# Arduino-Pro-Mini-v10.net
KiCad netlist of a schematic drawn in EAGLE
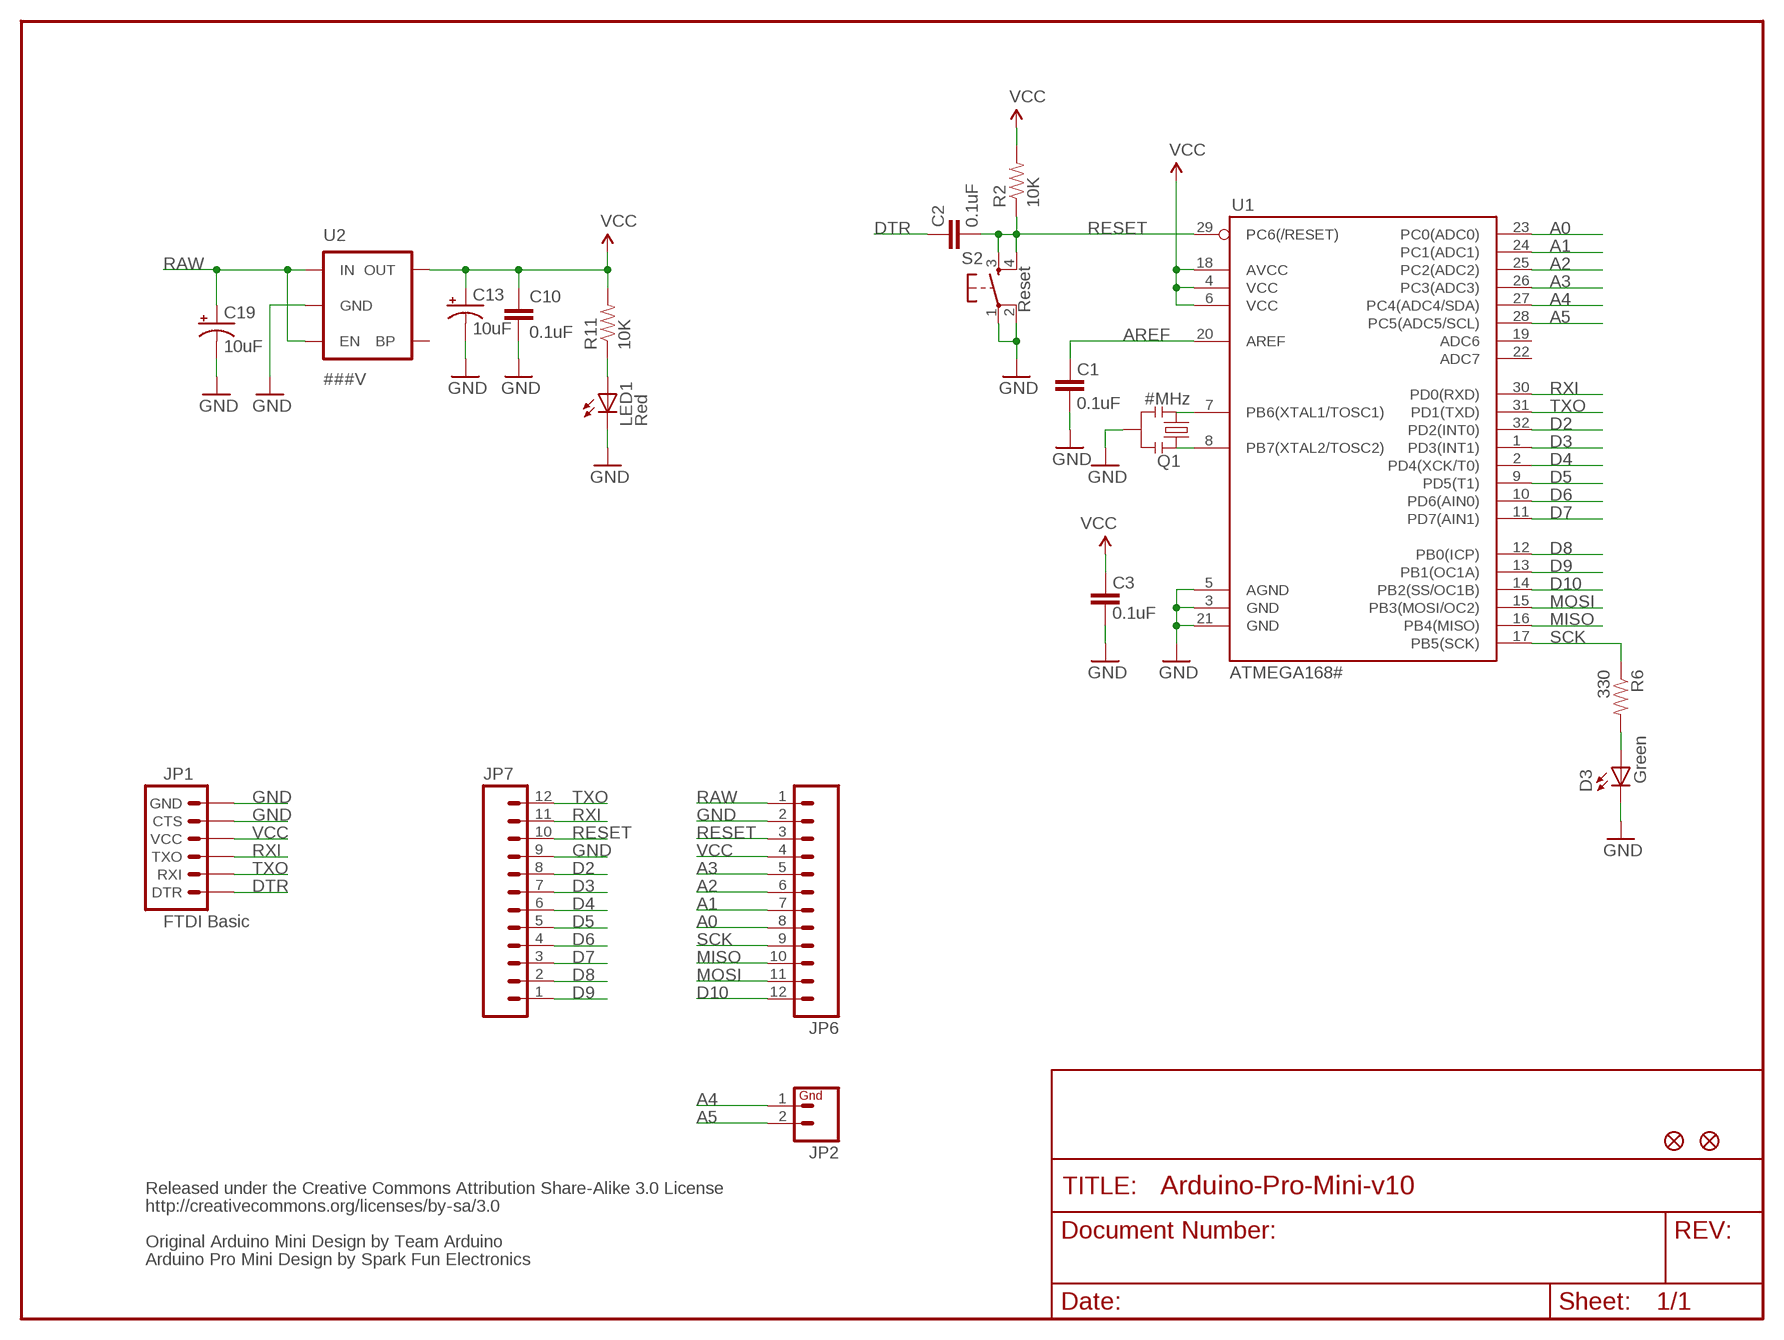
[diagram p0: schematic, sheet 1]

(export (version "E")
  (design (tool "Eeschema 10.0.6"))
  (components
    (comp (ref "C1")
      (value "0.1uF")
      (footprint "eagle-import:C0402")
      (libsource (lib "eagle-import") (part "CAP0402"))
    )
    (comp (ref "C2")
      (value "0.1uF")
      (footprint "eagle-import:C0402")
      (libsource (lib "eagle-import") (part "CAP0402"))
    )
    (comp (ref "C3")
      (value "0.1uF")
      (footprint "eagle-import:C0402")
      (libsource (lib "eagle-import") (part "CAP0402"))
    )
    (comp (ref "C10")
      (value "0.1uF")
      (footprint "eagle-import:C0402")
      (libsource (lib "eagle-import") (part "CAP0402"))
    )
    (comp (ref "C13")
      (value "10uF")
      (footprint "eagle-import:EIA3216")
      (libsource (lib "eagle-import") (part "CAP_POL1206"))
    )
    (comp (ref "C19")
      (value "10uF")
      (footprint "eagle-import:EIA3216")
      (libsource (lib "eagle-import") (part "CAP_POL1206"))
    )
    (comp (ref "D3")
      (value "Green")
      (footprint "eagle-import:LED-0603")
      (libsource (lib "eagle-import") (part "LED0603"))
    )
    (comp (ref "JP1")
      (value "FTDI Basic")
      (footprint "eagle-import:1X06")
      (libsource (lib "eagle-import") (part "ARDUINO_SERIAL_PROGRAMPTH"))
    )
    (comp (ref "JP2")
      (value "M02PTH")
      (footprint "eagle-import:1X02")
      (libsource (lib "eagle-import") (part "M02PTH"))
    )
    (comp (ref "JP6")
      (value "M12PTH")
      (footprint "eagle-import:1X12")
      (libsource (lib "eagle-import") (part "M12PTH"))
    )
    (comp (ref "JP7")
      (value "M12PTH")
      (footprint "eagle-import:1X12")
      (libsource (lib "eagle-import") (part "M12PTH"))
    )
    (comp (ref "LED1")
      (value "Red")
      (footprint "eagle-import:LED-0603")
      (libsource (lib "eagle-import") (part "LED0603"))
    )
    (comp (ref "Q1")
      (value "#MHz")
      (footprint "eagle-import:RESONATOR-SMD")
      (libsource (lib "eagle-import") (part "RESONATORSMD"))
    )
    (comp (ref "R2")
      (value "10K")
      (footprint "eagle-import:C0402")
      (libsource (lib "eagle-import") (part "RESISTOR0402"))
    )
    (comp (ref "R6")
      (value "330")
      (footprint "eagle-import:C0402")
      (libsource (lib "eagle-import") (part "RESISTOR0402"))
    )
    (comp (ref "R11")
      (value "10K")
      (footprint "eagle-import:C0402")
      (libsource (lib "eagle-import") (part "RESISTOR0402"))
    )
    (comp (ref "S2")
      (value "Reset")
      (footprint "eagle-import:TACTILE_SWITCH_SMD")
      (libsource (lib "eagle-import") (part "TAC_SWITCHSND"))
    )
    (comp (ref "U$2")
      (value "FIDUCIAL1X2")
      (footprint "eagle-import:FIDUCIAL-1X2")
      (libsource (lib "eagle-import") (part "FIDUCIAL1X2"))
    )
    (comp (ref "U$4")
      (value "FIDUCIAL1X2")
      (footprint "eagle-import:FIDUCIAL-1X2")
      (libsource (lib "eagle-import") (part "FIDUCIAL1X2"))
    )
    (comp (ref "U1")
      (value "ATMEGA168#")
      (footprint "eagle-import:TQFP32-08")
      (libsource (lib "eagle-import") (part "ATMEGA168"))
    )
    (comp (ref "U2")
      (value "###V")
      (footprint "eagle-import:SOT23-5")
      (libsource (lib "eagle-import") (part "V_REG_LDOSMD"))
    )
  )
  (nets
    (net (code "1") (name "/A0") (class "Default")
      (node (ref "JP6") (pin "8") (pinfunction "8_8") (pintype "passive"))
      (node (ref "U1") (pin "23") (pinfunction "PC0(ADC0)_23") (pintype "bidirectional"))
    )
    (net (code "2") (name "/A1") (class "Default")
      (node (ref "JP6") (pin "7") (pinfunction "7_7") (pintype "passive"))
      (node (ref "U1") (pin "24") (pinfunction "PC1(ADC1)_24") (pintype "bidirectional"))
    )
    (net (code "3") (name "/A2") (class "Default")
      (node (ref "JP6") (pin "6") (pinfunction "6_6") (pintype "passive"))
      (node (ref "U1") (pin "25") (pinfunction "PC2(ADC2)_25") (pintype "bidirectional"))
    )
    (net (code "4") (name "/A3") (class "Default")
      (node (ref "JP6") (pin "5") (pinfunction "5_5") (pintype "passive"))
      (node (ref "U1") (pin "26") (pinfunction "PC3(ADC3)_26") (pintype "bidirectional"))
    )
    (net (code "5") (name "/A4") (class "Default")
      (node (ref "JP2") (pin "1") (pinfunction "1_1") (pintype "passive"))
      (node (ref "U1") (pin "27") (pinfunction "PC4(ADC4/SDA)_27") (pintype "bidirectional"))
    )
    (net (code "6") (name "/A5") (class "Default")
      (node (ref "JP2") (pin "2") (pinfunction "2_2") (pintype "passive"))
      (node (ref "U1") (pin "28") (pinfunction "PC5(ADC5/SCL)_28") (pintype "bidirectional"))
    )
    (net (code "7") (name "/AREF") (class "Default")
      (node (ref "C1") (pin "2") (pinfunction "2_2") (pintype "passive"))
      (node (ref "U1") (pin "20") (pinfunction "AREF_20") (pintype "bidirectional"))
    )
    (net (code "8") (name "/D2") (class "Default")
      (node (ref "JP7") (pin "8") (pinfunction "8_8") (pintype "passive"))
      (node (ref "U1") (pin "32") (pinfunction "PD2(INT0)_32") (pintype "bidirectional"))
    )
    (net (code "9") (name "/D3") (class "Default")
      (node (ref "JP7") (pin "7") (pinfunction "7_7") (pintype "passive"))
      (node (ref "U1") (pin "1") (pinfunction "PD3(INT1)_1") (pintype "bidirectional"))
    )
    (net (code "10") (name "/D4") (class "Default")
      (node (ref "JP7") (pin "6") (pinfunction "6_6") (pintype "passive"))
      (node (ref "U1") (pin "2") (pinfunction "PD4(XCK/T0)_2") (pintype "bidirectional"))
    )
    (net (code "11") (name "/D5") (class "Default")
      (node (ref "JP7") (pin "5") (pinfunction "5_5") (pintype "passive"))
      (node (ref "U1") (pin "9") (pinfunction "PD5(T1)_9") (pintype "bidirectional"))
    )
    (net (code "12") (name "/D6") (class "Default")
      (node (ref "JP7") (pin "4") (pinfunction "4_4") (pintype "passive"))
      (node (ref "U1") (pin "10") (pinfunction "PD6(AIN0)_10") (pintype "bidirectional"))
    )
    (net (code "13") (name "/D7") (class "Default")
      (node (ref "JP7") (pin "3") (pinfunction "3_3") (pintype "passive"))
      (node (ref "U1") (pin "11") (pinfunction "PD7(AIN1)_11") (pintype "bidirectional"))
    )
    (net (code "14") (name "/D8") (class "Default")
      (node (ref "JP7") (pin "2") (pinfunction "2_2") (pintype "passive"))
      (node (ref "U1") (pin "12") (pinfunction "PB0(ICP)_12") (pintype "bidirectional"))
    )
    (net (code "15") (name "/D9") (class "Default")
      (node (ref "JP7") (pin "1") (pinfunction "1_1") (pintype "passive"))
      (node (ref "U1") (pin "13") (pinfunction "PB1(OC1A)_13") (pintype "bidirectional"))
    )
    (net (code "16") (name "/D10") (class "Default")
      (node (ref "JP6") (pin "12") (pinfunction "12_12") (pintype "passive"))
      (node (ref "U1") (pin "14") (pinfunction "PB2(SS/OC1B)_14") (pintype "bidirectional"))
    )
    (net (code "17") (name "/DTR") (class "Default")
      (node (ref "C2") (pin "2") (pinfunction "2_2") (pintype "passive"))
      (node (ref "JP1") (pin "1") (pinfunction "DTR_1") (pintype "passive"))
    )
    (net (code "18") (name "/MISO") (class "Default")
      (node (ref "JP6") (pin "10") (pinfunction "10_10") (pintype "passive"))
      (node (ref "U1") (pin "16") (pinfunction "PB4(MISO)_16") (pintype "bidirectional"))
    )
    (net (code "19") (name "/MOSI") (class "Default")
      (node (ref "JP6") (pin "11") (pinfunction "11_11") (pintype "passive"))
      (node (ref "U1") (pin "15") (pinfunction "PB3(MOSI/OC2)_15") (pintype "bidirectional"))
    )
    (net (code "20") (name "/RAW") (class "Default")
      (node (ref "C19") (pin "A") (pinfunction "+_A") (pintype "passive"))
      (node (ref "JP6") (pin "1") (pinfunction "1_1") (pintype "passive"))
      (node (ref "U2") (pin "1") (pinfunction "IN_1") (pintype "input"))
      (node (ref "U2") (pin "3") (pinfunction "EN_3") (pintype "input"))
    )
    (net (code "21") (name "/RESET") (class "Default")
      (node (ref "C2") (pin "1") (pinfunction "1_1") (pintype "passive"))
      (node (ref "JP6") (pin "3") (pinfunction "3_3") (pintype "passive"))
      (node (ref "JP7") (pin "10") (pinfunction "10_10") (pintype "passive"))
      (node (ref "R2") (pin "1") (pinfunction "1_1") (pintype "passive"))
      (node (ref "S2") (pin "3") (pinfunction "3_3") (pintype "passive"))
      (node (ref "S2") (pin "4") (pinfunction "4_4") (pintype "passive"))
      (node (ref "U1") (pin "29") (pinfunction "PC6(/RESET)_29") (pintype "bidirectional"))
    )
    (net (code "22") (name "/RXI") (class "Default")
      (node (ref "JP1") (pin "3") (pinfunction "TXO_3") (pintype "passive"))
      (node (ref "JP7") (pin "11") (pinfunction "11_11") (pintype "passive"))
      (node (ref "U1") (pin "30") (pinfunction "PD0(RXD)_30") (pintype "bidirectional"))
    )
    (net (code "23") (name "/SCK") (class "Default")
      (node (ref "JP6") (pin "9") (pinfunction "9_9") (pintype "passive"))
      (node (ref "R6") (pin "1") (pinfunction "1_1") (pintype "passive"))
      (node (ref "U1") (pin "17") (pinfunction "PB5(SCK)_17") (pintype "bidirectional"))
    )
    (net (code "24") (name "/TXO") (class "Default")
      (node (ref "JP1") (pin "2") (pinfunction "RXI_2") (pintype "passive"))
      (node (ref "JP7") (pin "12") (pinfunction "12_12") (pintype "passive"))
      (node (ref "U1") (pin "31") (pinfunction "PD1(TXD)_31") (pintype "bidirectional"))
    )
    (net (code "25") (name "GND") (class "Default")
      (node (ref "C1") (pin "1") (pinfunction "1_1") (pintype "passive"))
      (node (ref "C10") (pin "2") (pinfunction "2_2") (pintype "passive"))
      (node (ref "C13") (pin "C") (pinfunction "-_C") (pintype "passive"))
      (node (ref "C19") (pin "C") (pinfunction "-_C") (pintype "passive"))
      (node (ref "C3") (pin "1") (pinfunction "1_1") (pintype "passive"))
      (node (ref "D3") (pin "C") (pinfunction "C_C") (pintype "passive"))
      (node (ref "JP1") (pin "5") (pinfunction "CTS_5") (pintype "passive"))
      (node (ref "JP1") (pin "6") (pinfunction "GND_6") (pintype "passive"))
      (node (ref "JP6") (pin "2") (pinfunction "2_2") (pintype "passive"))
      (node (ref "JP7") (pin "9") (pinfunction "9_9") (pintype "passive"))
      (node (ref "LED1") (pin "C") (pinfunction "C_C") (pintype "passive"))
      (node (ref "Q1") (pin "2") (pinfunction "2_2") (pintype "passive"))
      (node (ref "S2") (pin "1") (pinfunction "1_1") (pintype "passive"))
      (node (ref "S2") (pin "2") (pinfunction "2_2") (pintype "passive"))
      (node (ref "U1") (pin "21") (pinfunction "GND_21") (pintype "bidirectional"))
      (node (ref "U1") (pin "3") (pinfunction "GND_3") (pintype "bidirectional"))
      (node (ref "U1") (pin "5") (pinfunction "AGND_5") (pintype "bidirectional"))
      (node (ref "U2") (pin "2") (pinfunction "GND_2") (pintype "input"))
    )
    (net (code "26") (name "Net-(D3-PadA)") (class "Default")
      (node (ref "D3") (pin "A") (pinfunction "A_A") (pintype "passive"))
      (node (ref "R6") (pin "2") (pinfunction "2_2") (pintype "passive"))
    )
    (net (code "27") (name "Net-(LED1-PadA)") (class "Default")
      (node (ref "LED1") (pin "A") (pinfunction "A_A") (pintype "passive"))
      (node (ref "R11") (pin "1") (pinfunction "1_1") (pintype "passive"))
    )
    (net (code "28") (name "Net-(U1-PB6(XTAL1{slash}TOSC1))") (class "Default")
      (node (ref "Q1") (pin "3") (pinfunction "3_3") (pintype "passive"))
      (node (ref "U1") (pin "7") (pinfunction "PB6(XTAL1/TOSC1)_7") (pintype "bidirectional"))
    )
    (net (code "29") (name "Net-(U1-PB7(XTAL2{slash}TOSC2))") (class "Default")
      (node (ref "Q1") (pin "1") (pinfunction "1_1") (pintype "passive"))
      (node (ref "U1") (pin "8") (pinfunction "PB7(XTAL2/TOSC2)_8") (pintype "bidirectional"))
    )
    (net (code "30") (name "VCC") (class "Default")
      (node (ref "C10") (pin "1") (pinfunction "1_1") (pintype "passive"))
      (node (ref "C13") (pin "A") (pinfunction "+_A") (pintype "passive"))
      (node (ref "C3") (pin "2") (pinfunction "2_2") (pintype "passive"))
      (node (ref "JP1") (pin "4") (pinfunction "VCC_4") (pintype "passive"))
      (node (ref "JP6") (pin "4") (pinfunction "4_4") (pintype "passive"))
      (node (ref "R11") (pin "2") (pinfunction "2_2") (pintype "passive"))
      (node (ref "R2") (pin "2") (pinfunction "2_2") (pintype "passive"))
      (node (ref "U1") (pin "18") (pinfunction "AVCC_18") (pintype "bidirectional"))
      (node (ref "U1") (pin "4") (pinfunction "VCC_4") (pintype "bidirectional"))
      (node (ref "U1") (pin "6") (pinfunction "VCC_6") (pintype "bidirectional"))
      (node (ref "U2") (pin "5") (pinfunction "OUT_5") (pintype "passive"))
    )
    (net (code "31") (name "unconnected-(U1-ADC6-Pad19)") (class "Default")
      (node (ref "U1") (pin "19") (pinfunction "ADC6_19") (pintype "bidirectional"))
    )
    (net (code "32") (name "unconnected-(U1-ADC7-Pad22)") (class "Default")
      (node (ref "U1") (pin "22") (pinfunction "ADC7_22") (pintype "bidirectional"))
    )
    (net (code "33") (name "unconnected-(U2-BP-Pad4)") (class "Default")
      (node (ref "U2") (pin "4") (pinfunction "BP_4") (pintype "input"))
    )
  )
)
